# schematic_eagle.net
KiCad netlist of a schematic drawn in EAGLE
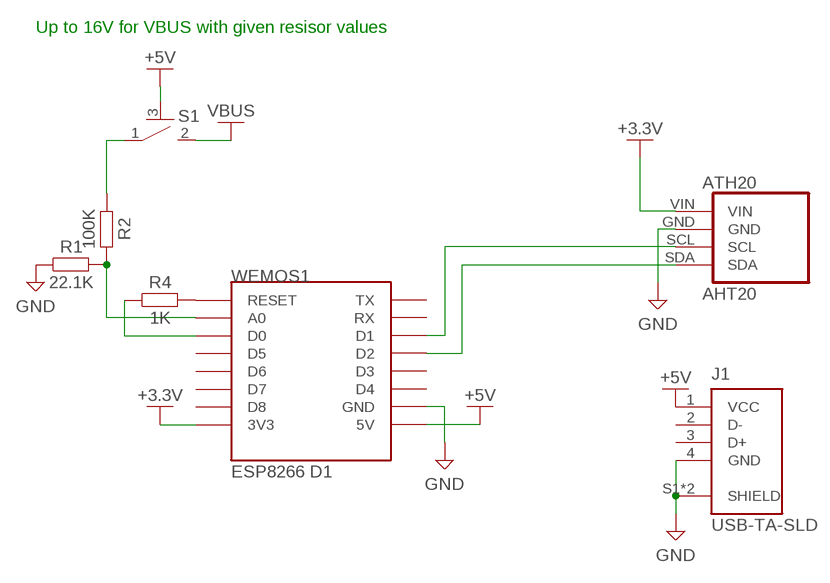
[diagram p0: schematic, sheet 1]

(export (version "E")
  (design (tool "Eeschema 10.0.6"))
  (components
    (comp (ref "ATH20")
      (value "AHT20")
      (footprint "eagle-import:AHT20")
      (libsource (lib "eagle-import") (part "AHT20"))
    )
    (comp (ref "J1")
      (value "USB-TA-SLD")
      (footprint "eagle-import:USB-TA-SLD")
      (fields (field (name "MANUFACTURER") "Molex"))
      (libsource (lib "eagle-import") (part "USB-TA-SLD"))
    )
    (comp (ref "R1")
      (value "22.1K")
      (footprint "eagle-import:RESC2012X65")
      (libsource (lib "eagle-import") (part "RCHIP-0805(2012-METRIC)_"))
    )
    (comp (ref "R2")
      (value "100K")
      (footprint "eagle-import:RESC2012X65")
      (libsource (lib "eagle-import") (part "RCHIP-0805(2012-METRIC)_"))
    )
    (comp (ref "R4")
      (value "1K")
      (footprint "eagle-import:RESC2012X65")
      (libsource (lib "eagle-import") (part "RCHIP-0805(2012-METRIC)_"))
    )
    (comp (ref "S1")
      (value "SMD_SWB3U-1100P(M)1100P(M)")
      (footprint "eagle-import:SMD_SW")
      (fields (field (name "MANUFACTURER") "Omron Electronics Inc-EMC Div") (field (name "MPN") "B3U-1100PM"))
      (libsource (lib "eagle-import") (part "SMD_SW1100P(M)B3U-1100P(M)"))
    )
    (comp (ref "WEMOS1")
      (value "U1")
      (footprint "eagle-import:WEMOS-D1-MINI")
      (fields (field (name "CN") "ESP8266 D1"))
      (libsource (lib "eagle-import") (part "WEMOS-D1-MINI"))
    )
  )
  (nets
    (net (code "1") (name "+3.3V") (class "Default")
      (node (ref "ATH20") (pin "VIN") (pinfunction "VIN_VIN") (pintype "power_in"))
      (node (ref "WEMOS1") (pin "3V3") (pinfunction "3V3_3V3") (pintype "bidirectional"))
    )
    (net (code "2") (name "+5V") (class "Default")
      (node (ref "J1") (pin "1") (pinfunction "VCC_1") (pintype "power_in"))
      (node (ref "S1") (pin "3") (pinfunction "3_3") (pintype "bidirectional"))
      (node (ref "WEMOS1") (pin "5V") (pinfunction "5V_5V") (pintype "bidirectional"))
    )
    (net (code "3") (name "GND") (class "Default")
      (node (ref "ATH20") (pin "GND") (pinfunction "GND_GND") (pintype "power_in"))
      (node (ref "J1") (pin "4") (pinfunction "GND_4") (pintype "power_in"))
      (node (ref "J1") (pin "S1") (pinfunction "SHIELD_S1") (pintype "passive"))
      (node (ref "J1") (pin "S2") (pinfunction "SHIELD_S2") (pintype "passive"))
      (node (ref "R1") (pin "1") (pinfunction "1_1") (pintype "passive"))
      (node (ref "WEMOS1") (pin "GND") (pinfunction "GND_GND") (pintype "bidirectional"))
    )
    (net (code "4") (name "Net-(ATH20-PadSCL)") (class "Default")
      (node (ref "ATH20") (pin "SCL") (pinfunction "SCL_SCL") (pintype "bidirectional"))
      (node (ref "WEMOS1") (pin "D1") (pinfunction "D1_D1") (pintype "bidirectional"))
    )
    (net (code "5") (name "Net-(ATH20-PadSDA)") (class "Default")
      (node (ref "ATH20") (pin "SDA") (pinfunction "SDA_SDA") (pintype "bidirectional"))
      (node (ref "WEMOS1") (pin "D2") (pinfunction "D2_D2") (pintype "bidirectional"))
    )
    (net (code "6") (name "Net-(R1-Pad2)") (class "Default")
      (node (ref "R1") (pin "2") (pinfunction "2_2") (pintype "passive"))
      (node (ref "R2") (pin "2") (pinfunction "2_2") (pintype "passive"))
      (node (ref "WEMOS1") (pin "A0") (pinfunction "A0_A0") (pintype "bidirectional"))
    )
    (net (code "7") (name "Net-(R2-Pad1)") (class "Default")
      (node (ref "R2") (pin "1") (pinfunction "1_1") (pintype "passive"))
      (node (ref "S1") (pin "1") (pinfunction "1_1") (pintype "bidirectional"))
    )
    (net (code "8") (name "Net-(R4-Pad1)") (class "Default")
      (node (ref "R4") (pin "1") (pinfunction "1_1") (pintype "passive"))
      (node (ref "WEMOS1") (pin "D0") (pinfunction "D0_D0") (pintype "bidirectional"))
    )
    (net (code "9") (name "Net-(R4-Pad2)") (class "Default")
      (node (ref "R4") (pin "2") (pinfunction "2_2") (pintype "passive"))
      (node (ref "WEMOS1") (pin "RESET") (pinfunction "RESET_RESET") (pintype "bidirectional"))
    )
    (net (code "10") (name "VBUS") (class "Default")
      (node (ref "S1") (pin "2") (pinfunction "2_2") (pintype "bidirectional"))
    )
    (net (code "11") (name "unconnected-(J1-D+-Pad3)") (class "Default")
      (node (ref "J1") (pin "3") (pinfunction "D+_3") (pintype "bidirectional"))
    )
    (net (code "12") (name "unconnected-(J1-D--Pad2)") (class "Default")
      (node (ref "J1") (pin "2") (pinfunction "D-_2") (pintype "bidirectional"))
    )
    (net (code "13") (name "unconnected-(WEMOS1-PadD3)") (class "Default")
      (node (ref "WEMOS1") (pin "D3") (pinfunction "D3_D3") (pintype "bidirectional"))
    )
    (net (code "14") (name "unconnected-(WEMOS1-PadD4)") (class "Default")
      (node (ref "WEMOS1") (pin "D4") (pinfunction "D4_D4") (pintype "bidirectional"))
    )
    (net (code "15") (name "unconnected-(WEMOS1-PadD5)") (class "Default")
      (node (ref "WEMOS1") (pin "D5") (pinfunction "D5_D5") (pintype "bidirectional"))
    )
    (net (code "16") (name "unconnected-(WEMOS1-PadD6)") (class "Default")
      (node (ref "WEMOS1") (pin "D6") (pinfunction "D6_D6") (pintype "bidirectional"))
    )
    (net (code "17") (name "unconnected-(WEMOS1-PadD7)") (class "Default")
      (node (ref "WEMOS1") (pin "D7") (pinfunction "D7_D7") (pintype "bidirectional"))
    )
    (net (code "18") (name "unconnected-(WEMOS1-PadD8)") (class "Default")
      (node (ref "WEMOS1") (pin "D8") (pinfunction "D8_D8") (pintype "bidirectional"))
    )
    (net (code "19") (name "unconnected-(WEMOS1-PadRX)") (class "Default")
      (node (ref "WEMOS1") (pin "RX") (pinfunction "RX_RX") (pintype "bidirectional"))
    )
    (net (code "20") (name "unconnected-(WEMOS1-PadTX)") (class "Default")
      (node (ref "WEMOS1") (pin "TX") (pinfunction "TX_TX") (pintype "bidirectional"))
    )
  )
)
